# Placa_Final_Embebidos_MCU.net
KiCad netlist of a schematic drawn in Altium Designer
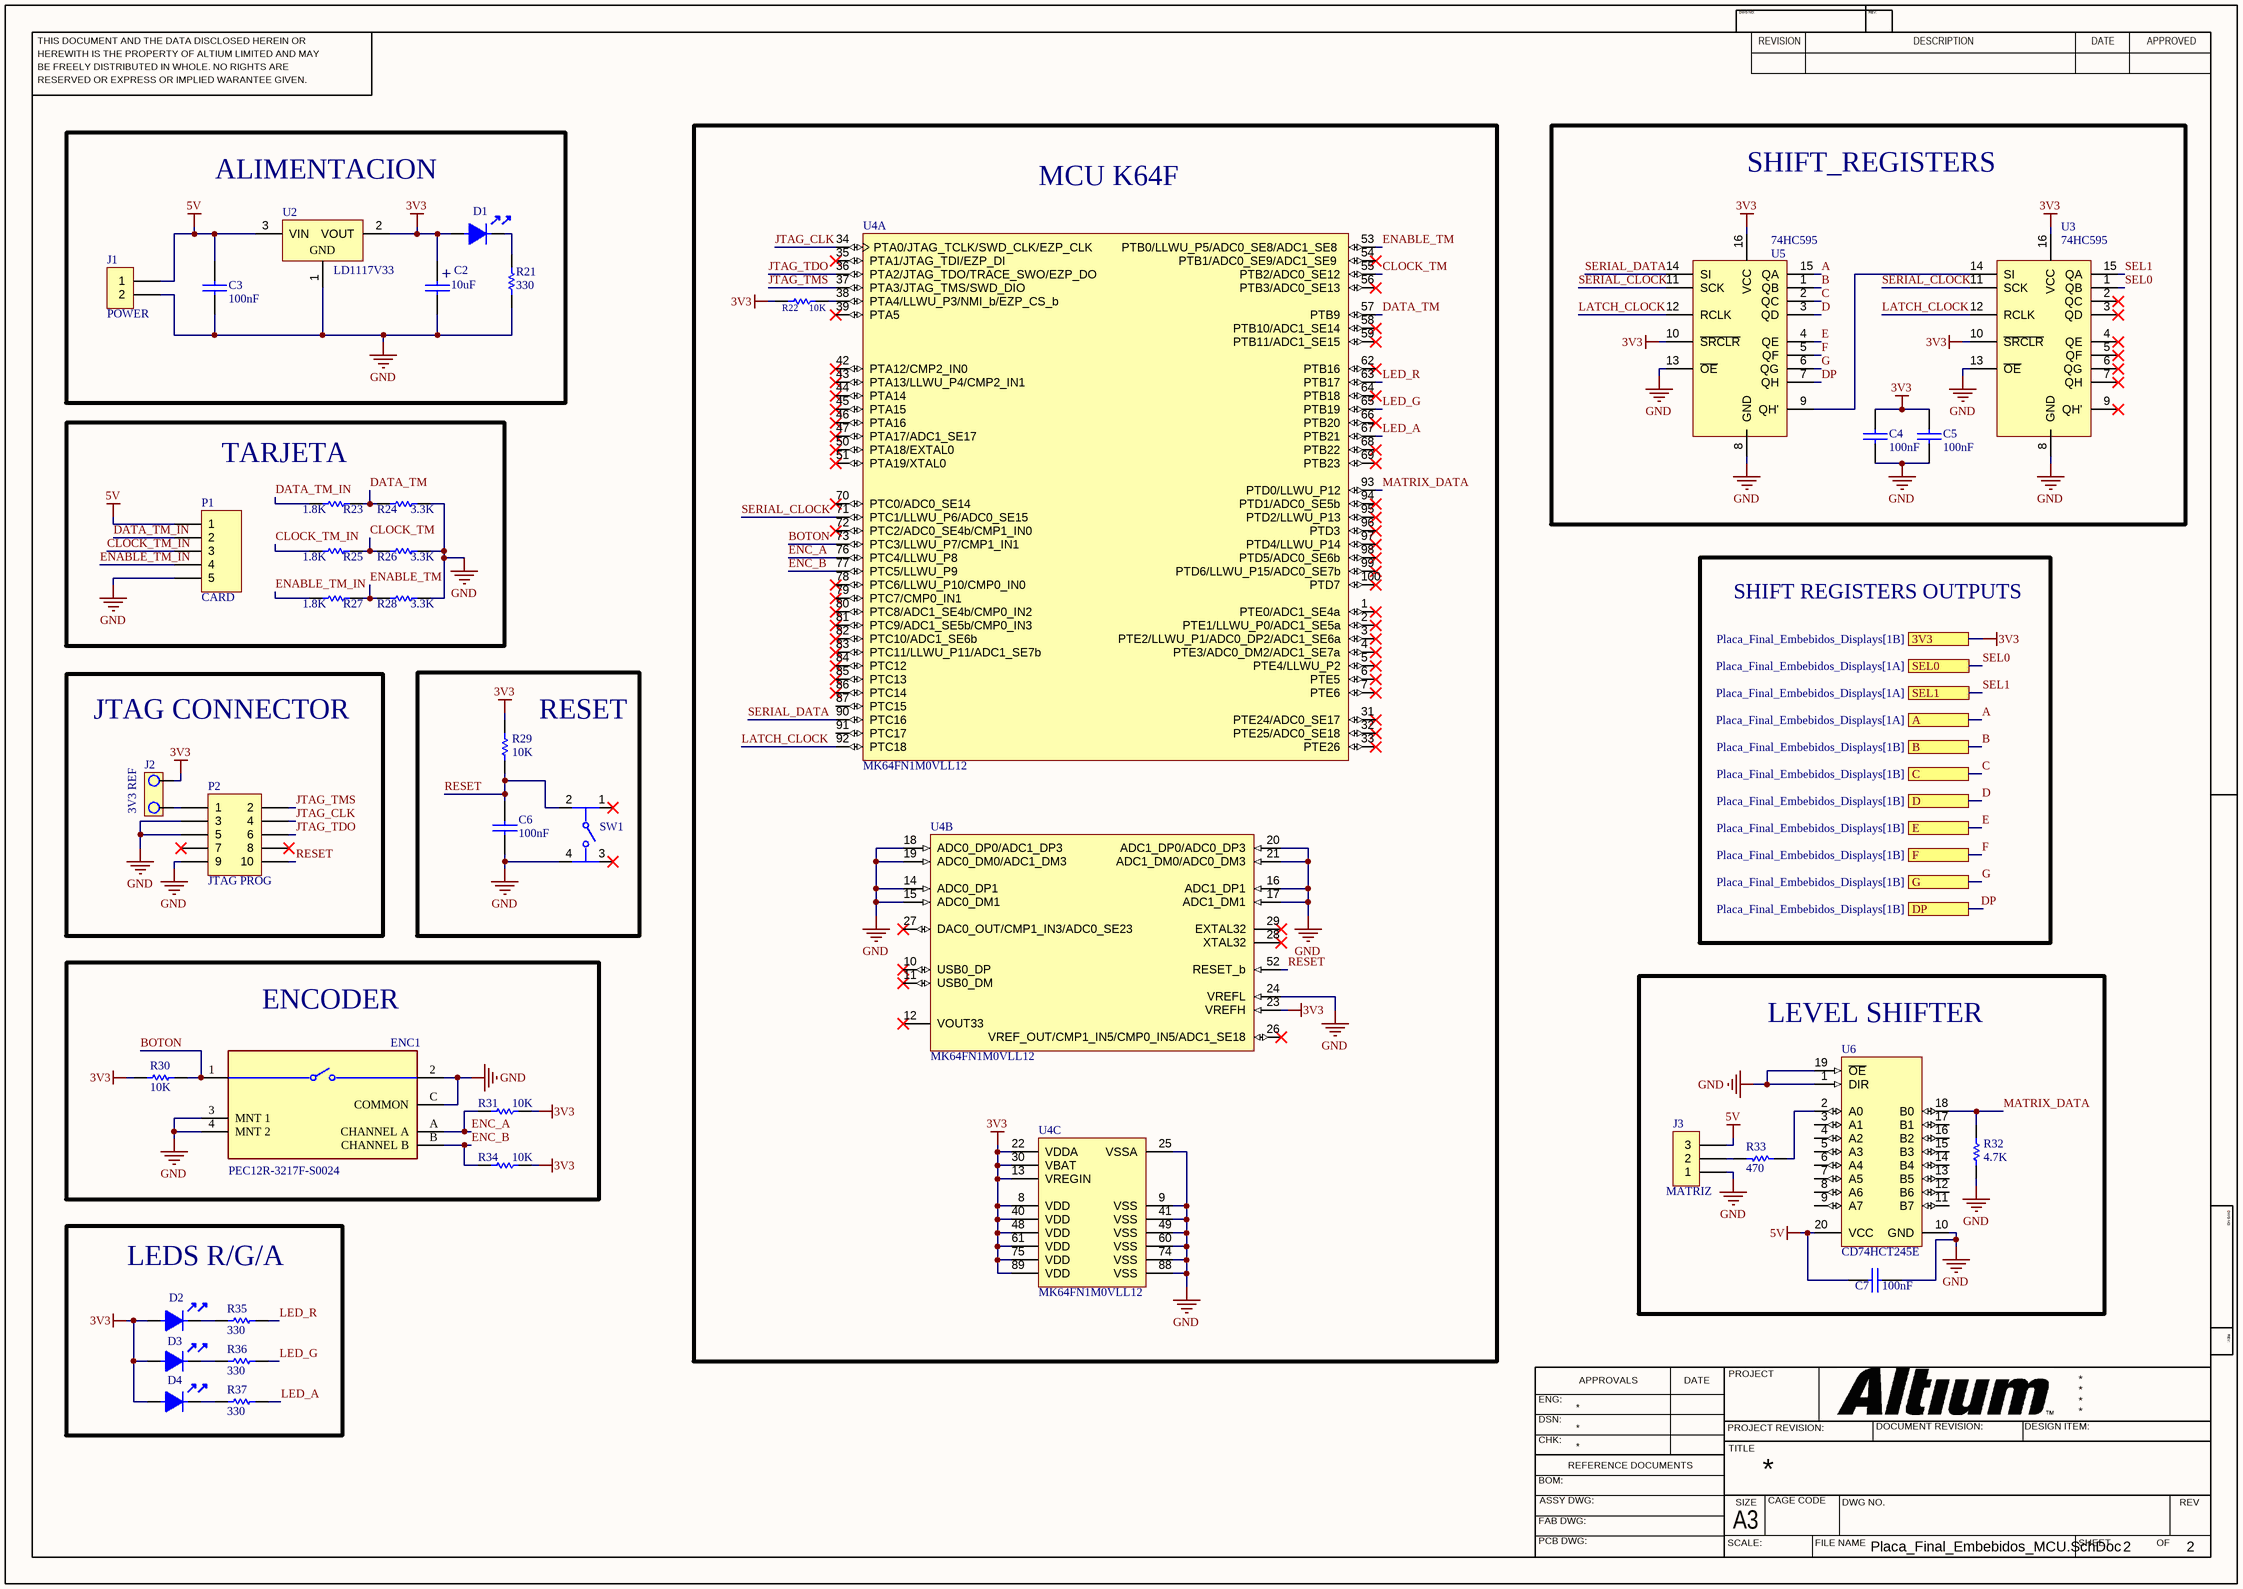
[diagram p0: Placa_Final_Embebidos_MCU.SchDoc]

(export (version "E")
  (design (tool "Eeschema 10.0.6"))
  (components
    (comp (ref "C2") (value "10uF") (footprint "CAP100RP") (libsource (lib "LIB PIO IX") (part "CAPPOL")))
    (comp (ref "C3") (value "100nF") (footprint "CAP200") (libsource (lib "LIB PIO IX") (part "CAP")))
    (comp (ref "C4") (value "100nF") (footprint "CAP200") (libsource (lib "LIB PIO IX") (part "CAP")))
    (comp (ref "C5") (value "100nF") (footprint "CAP200") (libsource (lib "LIB PIO IX") (part "CAP")))
    (comp (ref "C6") (value "100nF") (footprint "CAP200") (libsource (lib "LIB PIO IX") (part "CAP")))
    (comp (ref "C7") (value "100nF") (footprint "CAP200") (libsource (lib "LIB PIO IX") (part "CAP")))
    (comp (ref "D1") (value "~") (footprint "LED3") (libsource (lib "LIB PIO IX") (part "LED")))
    (comp (ref "D2") (value "~") (footprint "LED3") (libsource (lib "LIB PIO IX") (part "LED")))
    (comp (ref "D3") (value "~") (footprint "LED3") (libsource (lib "LIB PIO IX") (part "LED")))
    (comp (ref "D4") (value "~") (footprint "LED3") (libsource (lib "LIB PIO IX") (part "LED")))
    (comp (ref "ENC1")
      (value "PEC12R-3217F-S0024")
      (footprint "FP-PEC12R-3217F-S0024-MFG")
      (description "ROTARY ENCODER")
      (libsource (lib "Altium Content Vault") (part "795c46dd6d7d77f565e7c060d07d204"))
    )
    (comp (ref "J1") (value "POWER") (footprint "BORNERA2") (libsource (lib "LIBEBAL") (part "BORNERA 2")))
    (comp (ref "J2") (value "3V3 REF") (footprint "JUMPER2") (libsource (lib "LIBEBAL") (part "JUMPER")))
    (comp (ref "J3") (value "MATRIZ") (footprint "SIP3") (libsource (lib "LIBEBAL") (part "CON3")))
    (comp (ref "P1")
      (value "CARD")
      (footprint "HDR1X5")
      (description "Header, 5-Pin")
      (fields (field (name "PUBLISHER") "Altium Limited"))
      (libsource (lib "Miscellaneous Connectors") (part "Header 5"))
    )
    (comp (ref "P2")
      (value "JTAG PROG")
      (footprint "HDR2X5")
      (description "Header, 5-Pin, Dual row")
      (fields (field (name "PUBLISHER") "Altium Limited"))
      (libsource (lib "Miscellaneous Connectors") (part "Header 5X2"))
    )
    (comp (ref "R21") (value "330") (footprint "RES400") (libsource (lib "LIB PIO IX") (part "RES")))
    (comp (ref "R22") (value "10K") (footprint "RES400") (libsource (lib "LIB PIO IX") (part "RES")))
    (comp (ref "R23") (value "1.8K") (footprint "RES400") (libsource (lib "LIB PIO IX") (part "RES")))
    (comp (ref "R24") (value "3.3K") (footprint "RES400") (libsource (lib "LIB PIO IX") (part "RES")))
    (comp (ref "R25") (value "1.8K") (footprint "RES400") (libsource (lib "LIB PIO IX") (part "RES")))
    (comp (ref "R26") (value "3.3K") (footprint "RES400") (libsource (lib "LIB PIO IX") (part "RES")))
    (comp (ref "R27") (value "1.8K") (footprint "RES400") (libsource (lib "LIB PIO IX") (part "RES")))
    (comp (ref "R28") (value "3.3K") (footprint "RES400") (libsource (lib "LIB PIO IX") (part "RES")))
    (comp (ref "R29") (value "10K") (footprint "RES400") (libsource (lib "LIB PIO IX") (part "RES")))
    (comp (ref "R30") (value "10K") (footprint "RES400") (libsource (lib "LIB PIO IX") (part "RES")))
    (comp (ref "R31") (value "10K") (footprint "RES400") (libsource (lib "LIB PIO IX") (part "RES")))
    (comp (ref "R32") (value "4.7K") (footprint "RES400") (libsource (lib "LIB PIO IX") (part "RES")))
    (comp (ref "R33") (value "470") (footprint "RES400") (libsource (lib "LIB PIO IX") (part "RES")))
    (comp (ref "R34") (value "10K") (footprint "RES400") (libsource (lib "LIB PIO IX") (part "RES")))
    (comp (ref "R35") (value "330") (footprint "RES400") (libsource (lib "LIB PIO IX") (part "RES")))
    (comp (ref "R36") (value "330") (footprint "RES400") (libsource (lib "LIB PIO IX") (part "RES")))
    (comp (ref "R37") (value "330") (footprint "RES400") (libsource (lib "LIB PIO IX") (part "RES")))
    (comp (ref "SW1")
      (value "~")
      (footprint "FP-B3F-1055-MFG")
      (description "SWITCH TACTILE SPST-NO 0.05A 24V")
      (libsource (lib "Altium Content Vault") (part "b8895f3f4cefb76e1819d2863dba89b"))
    )
    (comp (ref "U2")
      (value "LD1117V33")
      (footprint "TO220")
      (description "Fixed Low Drop Positive Voltage Regulator, 3.3V, 3-Pin TO-220")
      (libsource (lib "Altium Content Vault") (part "PM-REG-LD1117V-SIL3"))
    )
    (comp (ref "U3") (value "74HC595") (footprint "DIP16") (libsource (lib "LIBEBAL") (part "74HC595")))
    (comp (ref "U4")
      (value "MK64FN1M0VLL12")
      (footprint "PCB_BOARD_K64F_MIRROR:K64F_DevBoard_Headers_MIRROR")
      (fields (field (name "MANUFACTURER") "Freescale Semiconductor"))
      (libsource (lib "K64F_Board_MIRROR") (part "CMP-0182-00049-1"))
    )
    (comp (ref "U5") (value "74HC595") (footprint "DIP16") (libsource (lib "LIBEBAL") (part "74HC595")))
    (comp (ref "U6")
      (value "CD74HCT245E")
      (footprint "N0020A")
      (description "High Speed CMOS Logic Non-Inverting Octal-Bus Transceiver with 3-State Outpus, N0020A, TUBE")
      (fields
        (field (name "GENERIC PART NUMBER") "CD74HCT245")
        (field (name "MANUFACTURER") "Texas Instruments")
      )
      (libsource (lib "Altium Content Vault") (part "TI-CD54_74XXX245_640-20"))
    )
  )
  (nets
    (net (code "1") (name "/A") (class "Default")
      (node (ref "U5") (pin "15") (pinfunction "QA_15") (pintype "passive"))
    )
    (net (code "2") (name "/B") (class "Default")
      (node (ref "U5") (pin "1") (pinfunction "QB_1") (pintype "passive"))
    )
    (net (code "3") (name "/BOTON") (class "Default")
      (node (ref "ENC1") (pin "1") (pinfunction "1_1") (pintype "passive"))
      (node (ref "R30") (pin "2") (pinfunction "2_2") (pintype "passive"))
      (node (ref "U4") (pin "73") (pinfunction "PTC3/LLWU_P7/CMP1_IN1_73") (pintype "bidirectional"))
    )
    (net (code "4") (name "/C") (class "Default")
      (node (ref "U5") (pin "2") (pinfunction "QC_2") (pintype "passive"))
    )
    (net (code "5") (name "/CLOCK_TM") (class "Default")
      (node (ref "R25") (pin "2") (pinfunction "2_2") (pintype "passive"))
      (node (ref "R26") (pin "1") (pinfunction "1_1") (pintype "passive"))
      (node (ref "U4") (pin "55") (pinfunction "PTB2/ADC0_SE12_55") (pintype "bidirectional"))
    )
    (net (code "6") (name "/CLOCK_TM_IN") (class "Default")
      (node (ref "P1") (pin "3") (pinfunction "3_3") (pintype "passive"))
      (node (ref "R25") (pin "1") (pinfunction "1_1") (pintype "passive"))
    )
    (net (code "7") (name "/D") (class "Default")
      (node (ref "U5") (pin "3") (pinfunction "QD_3") (pintype "passive"))
    )
    (net (code "8") (name "/DATA_TM") (class "Default")
      (node (ref "R23") (pin "2") (pinfunction "2_2") (pintype "passive"))
      (node (ref "R24") (pin "1") (pinfunction "1_1") (pintype "passive"))
      (node (ref "U4") (pin "57") (pinfunction "PTB9_57") (pintype "bidirectional"))
    )
    (net (code "9") (name "/DATA_TM_IN") (class "Default")
      (node (ref "P1") (pin "2") (pinfunction "2_2") (pintype "passive"))
      (node (ref "R23") (pin "1") (pinfunction "1_1") (pintype "passive"))
    )
    (net (code "10") (name "/DP") (class "Default")
      (node (ref "U5") (pin "7") (pinfunction "QH_7") (pintype "passive"))
    )
    (net (code "11") (name "/E") (class "Default")
      (node (ref "U5") (pin "4") (pinfunction "QE_4") (pintype "passive"))
    )
    (net (code "12") (name "/ENABLE_TM") (class "Default")
      (node (ref "R27") (pin "2") (pinfunction "2_2") (pintype "passive"))
      (node (ref "R28") (pin "1") (pinfunction "1_1") (pintype "passive"))
      (node (ref "U4") (pin "53") (pinfunction "PTB0/LLWU_P5/ADC0_SE8/ADC1_SE8_53") (pintype "bidirectional"))
    )
    (net (code "13") (name "/ENABLE_TM_IN") (class "Default")
      (node (ref "P1") (pin "4") (pinfunction "4_4") (pintype "passive"))
      (node (ref "R27") (pin "1") (pinfunction "1_1") (pintype "passive"))
    )
    (net (code "14") (name "/ENC_A") (class "Default")
      (node (ref "ENC1") (pin "A") (pinfunction "CHANNEL_A_A") (pintype "passive"))
      (node (ref "R31") (pin "1") (pinfunction "1_1") (pintype "passive"))
      (node (ref "U4") (pin "76") (pinfunction "PTC4/LLWU_P8_76") (pintype "bidirectional"))
    )
    (net (code "15") (name "/ENC_B") (class "Default")
      (node (ref "ENC1") (pin "B") (pinfunction "CHANNEL_B_B") (pintype "passive"))
      (node (ref "R34") (pin "2") (pinfunction "2_2") (pintype "passive"))
      (node (ref "U4") (pin "77") (pinfunction "PTC5/LLWU_P9_77") (pintype "bidirectional"))
    )
    (net (code "16") (name "/F") (class "Default")
      (node (ref "U5") (pin "5") (pinfunction "QF_5") (pintype "passive"))
    )
    (net (code "17") (name "/G") (class "Default")
      (node (ref "U5") (pin "6") (pinfunction "QG_6") (pintype "passive"))
    )
    (net (code "18") (name "/JTAG_CLK") (class "Default")
      (node (ref "P2") (pin "4") (pinfunction "4_4") (pintype "passive"))
      (node (ref "U4") (pin "34") (pinfunction "PTA0/JTAG_TCLK/SWD_CLK/EZP_CLK_34") (pintype "bidirectional"))
    )
    (net (code "19") (name "/JTAG_TDO") (class "Default")
      (node (ref "P2") (pin "6") (pinfunction "6_6") (pintype "passive"))
      (node (ref "U4") (pin "36") (pinfunction "PTA2/JTAG_TDO/TRACE_SWO/EZP_DO_36") (pintype "bidirectional"))
    )
    (net (code "20") (name "/JTAG_TMS") (class "Default")
      (node (ref "P2") (pin "2") (pinfunction "2_2") (pintype "passive"))
      (node (ref "U4") (pin "37") (pinfunction "PTA3/JTAG_TMS/SWD_DIO_37") (pintype "bidirectional"))
    )
    (net (code "21") (name "/LATCH_CLOCK") (class "Default")
      (node (ref "U3") (pin "12") (pinfunction "RCLK_12") (pintype "passive"))
      (node (ref "U4") (pin "92") (pinfunction "PTC18_92") (pintype "bidirectional"))
      (node (ref "U5") (pin "12") (pinfunction "RCLK_12") (pintype "passive"))
    )
    (net (code "22") (name "/LED_A") (class "Default")
      (node (ref "R37") (pin "2") (pinfunction "2_2") (pintype "passive"))
      (node (ref "U4") (pin "67") (pinfunction "PTB21_67") (pintype "bidirectional"))
    )
    (net (code "23") (name "/LED_G") (class "Default")
      (node (ref "R36") (pin "2") (pinfunction "2_2") (pintype "passive"))
      (node (ref "U4") (pin "65") (pinfunction "PTB19_65") (pintype "bidirectional"))
    )
    (net (code "24") (name "/LED_R") (class "Default")
      (node (ref "R35") (pin "2") (pinfunction "2_2") (pintype "passive"))
      (node (ref "U4") (pin "63") (pinfunction "PTB17_63") (pintype "bidirectional"))
    )
    (net (code "25") (name "/MATRIX_DATA") (class "Default")
      (node (ref "R32") (pin "2") (pinfunction "2_2") (pintype "passive"))
      (node (ref "U4") (pin "93") (pinfunction "PTD0/LLWU_P12_93") (pintype "bidirectional"))
      (node (ref "U6") (pin "18") (pinfunction "B0_18") (pintype "bidirectional"))
    )
    (net (code "26") (name "/RESET") (class "Default")
      (node (ref "C6") (pin "1") (pinfunction "1_1") (pintype "passive"))
      (node (ref "P2") (pin "10") (pinfunction "10_10") (pintype "passive"))
      (node (ref "R29") (pin "1") (pinfunction "1_1") (pintype "passive"))
      (node (ref "SW1") (pin "2") (pinfunction "2_2") (pintype "passive"))
      (node (ref "U4") (pin "52") (pinfunction "RESET_b_52") (pintype "input"))
    )
    (net (code "27") (name "/SEL0") (class "Default")
      (node (ref "U3") (pin "1") (pinfunction "QB_1") (pintype "passive"))
    )
    (net (code "28") (name "/SEL1") (class "Default")
      (node (ref "U3") (pin "15") (pinfunction "QA_15") (pintype "passive"))
    )
    (net (code "29") (name "/SERIAL_CLOCK") (class "Default")
      (node (ref "U3") (pin "11") (pinfunction "SCK_11") (pintype "passive"))
      (node (ref "U4") (pin "71") (pinfunction "PTC1/LLWU_P6/ADC0_SE15_71") (pintype "bidirectional"))
      (node (ref "U5") (pin "11") (pinfunction "SCK_11") (pintype "passive"))
    )
    (net (code "30") (name "/SERIAL_DATA") (class "Default")
      (node (ref "U4") (pin "90") (pinfunction "PTC16_90") (pintype "bidirectional"))
      (node (ref "U5") (pin "14") (pinfunction "SI_14") (pintype "passive"))
    )
    (net (code "31") (name "3V3") (class "Default")
      (node (ref "C2") (pin "1") (pinfunction "1_1") (pintype "passive"))
      (node (ref "C4") (pin "2") (pinfunction "2_2") (pintype "passive"))
      (node (ref "C5") (pin "2") (pinfunction "2_2") (pintype "passive"))
      (node (ref "D1") (pin "1") (pinfunction "1_1") (pintype "passive"))
      (node (ref "D2") (pin "1") (pinfunction "1_1") (pintype "passive"))
      (node (ref "D3") (pin "1") (pinfunction "1_1") (pintype "passive"))
      (node (ref "D4") (pin "1") (pinfunction "1_1") (pintype "passive"))
      (node (ref "J2") (pin "1") (pinfunction "1_1") (pintype "passive"))
      (node (ref "R22") (pin "2") (pinfunction "2_2") (pintype "passive"))
      (node (ref "R29") (pin "2") (pinfunction "2_2") (pintype "passive"))
      (node (ref "R30") (pin "1") (pinfunction "1_1") (pintype "passive"))
      (node (ref "R31") (pin "2") (pinfunction "2_2") (pintype "passive"))
      (node (ref "R34") (pin "1") (pinfunction "1_1") (pintype "passive"))
      (node (ref "U2") (pin "2") (pinfunction "VOUT_2") (pintype "power_in"))
      (node (ref "U3") (pin "10") (pinfunction "~{SRCLR}_10") (pintype "passive"))
      (node (ref "U3") (pin "16") (pinfunction "VCC_16") (pintype "passive"))
      (node (ref "U4") (pin "13") (pinfunction "VREGIN_13") (pintype "power_in"))
      (node (ref "U4") (pin "22") (pinfunction "VDDA_22") (pintype "power_in"))
      (node (ref "U4") (pin "23") (pinfunction "VREFH_23") (pintype "input"))
      (node (ref "U4") (pin "30") (pinfunction "VBAT_30") (pintype "power_in"))
      (node (ref "U4") (pin "40") (pinfunction "VDD_40") (pintype "power_in"))
      (node (ref "U4") (pin "48") (pinfunction "VDD_48") (pintype "power_in"))
      (node (ref "U4") (pin "61") (pinfunction "VDD_61") (pintype "power_in"))
      (node (ref "U4") (pin "75") (pinfunction "VDD_75") (pintype "power_in"))
      (node (ref "U4") (pin "8") (pinfunction "VDD_8") (pintype "power_in"))
      (node (ref "U4") (pin "89") (pinfunction "VDD_89") (pintype "power_in"))
      (node (ref "U5") (pin "10") (pinfunction "~{SRCLR}_10") (pintype "passive"))
      (node (ref "U5") (pin "16") (pinfunction "VCC_16") (pintype "passive"))
    )
    (net (code "32") (name "5V") (class "Default")
      (node (ref "C3") (pin "1") (pinfunction "1_1") (pintype "passive"))
      (node (ref "C7") (pin "1") (pinfunction "1_1") (pintype "passive"))
      (node (ref "J1") (pin "1") (pinfunction "1_1") (pintype "passive"))
      (node (ref "J3") (pin "3") (pinfunction "3_3") (pintype "passive"))
      (node (ref "P1") (pin "1") (pinfunction "1_1") (pintype "passive"))
      (node (ref "U2") (pin "3") (pinfunction "VIN_3") (pintype "power_in"))
      (node (ref "U6") (pin "20") (pinfunction "VCC_20") (pintype "power_in"))
    )
    (net (code "33") (name "GND") (class "Default")
      (node (ref "C2") (pin "2") (pinfunction "2_2") (pintype "passive"))
      (node (ref "C3") (pin "2") (pinfunction "2_2") (pintype "passive"))
      (node (ref "C4") (pin "1") (pinfunction "1_1") (pintype "passive"))
      (node (ref "C5") (pin "1") (pinfunction "1_1") (pintype "passive"))
      (node (ref "C6") (pin "2") (pinfunction "2_2") (pintype "passive"))
      (node (ref "C7") (pin "2") (pinfunction "2_2") (pintype "passive"))
      (node (ref "ENC1") (pin "2") (pinfunction "2_2") (pintype "passive"))
      (node (ref "ENC1") (pin "3") (pinfunction "MNT_1_3") (pintype "passive"))
      (node (ref "ENC1") (pin "4") (pinfunction "MNT_2_4") (pintype "passive"))
      (node (ref "ENC1") (pin "C") (pinfunction "COMMON_C") (pintype "passive"))
      (node (ref "J1") (pin "2") (pinfunction "2_2") (pintype "passive"))
      (node (ref "J3") (pin "1") (pinfunction "1_1") (pintype "passive"))
      (node (ref "P1") (pin "5") (pinfunction "5_5") (pintype "passive"))
      (node (ref "P2") (pin "3") (pinfunction "3_3") (pintype "passive"))
      (node (ref "P2") (pin "5") (pinfunction "5_5") (pintype "passive"))
      (node (ref "P2") (pin "9") (pinfunction "9_9") (pintype "passive"))
      (node (ref "R21") (pin "2") (pinfunction "2_2") (pintype "passive"))
      (node (ref "R24") (pin "2") (pinfunction "2_2") (pintype "passive"))
      (node (ref "R26") (pin "2") (pinfunction "2_2") (pintype "passive"))
      (node (ref "R28") (pin "2") (pinfunction "2_2") (pintype "passive"))
      (node (ref "R32") (pin "1") (pinfunction "1_1") (pintype "passive"))
      (node (ref "SW1") (pin "4") (pinfunction "4_4") (pintype "passive"))
      (node (ref "U2") (pin "1") (pinfunction "GND_1") (pintype "power_in"))
      (node (ref "U3") (pin "13") (pinfunction "~{OE}_13") (pintype "passive"))
      (node (ref "U3") (pin "8") (pinfunction "GND_8") (pintype "passive"))
      (node (ref "U4") (pin "14") (pinfunction "ADC0_DP1_14") (pintype "input"))
      (node (ref "U4") (pin "15") (pinfunction "ADC0_DM1_15") (pintype "input"))
      (node (ref "U4") (pin "16") (pinfunction "ADC1_DP1_16") (pintype "input"))
      (node (ref "U4") (pin "17") (pinfunction "ADC1_DM1_17") (pintype "input"))
      (node (ref "U4") (pin "18") (pinfunction "ADC0_DP0/ADC1_DP3_18") (pintype "input"))
      (node (ref "U4") (pin "19") (pinfunction "ADC0_DM0/ADC1_DM3_19") (pintype "input"))
      (node (ref "U4") (pin "20") (pinfunction "ADC1_DP0/ADC0_DP3_20") (pintype "input"))
      (node (ref "U4") (pin "21") (pinfunction "ADC1_DM0/ADC0_DM3_21") (pintype "input"))
      (node (ref "U4") (pin "24") (pinfunction "VREFL_24") (pintype "input"))
      (node (ref "U4") (pin "25") (pinfunction "VSSA_25") (pintype "power_in"))
      (node (ref "U4") (pin "41") (pinfunction "VSS_41") (pintype "power_in"))
      (node (ref "U4") (pin "49") (pinfunction "VSS_49") (pintype "power_in"))
      (node (ref "U4") (pin "60") (pinfunction "VSS_60") (pintype "power_in"))
      (node (ref "U4") (pin "74") (pinfunction "VSS_74") (pintype "power_in"))
      (node (ref "U4") (pin "88") (pinfunction "VSS_88") (pintype "power_in"))
      (node (ref "U4") (pin "9") (pinfunction "VSS_9") (pintype "power_in"))
      (node (ref "U5") (pin "13") (pinfunction "~{OE}_13") (pintype "passive"))
      (node (ref "U5") (pin "8") (pinfunction "GND_8") (pintype "passive"))
      (node (ref "U6") (pin "1") (pinfunction "DIR_1") (pintype "input"))
      (node (ref "U6") (pin "10") (pinfunction "GND_10") (pintype "power_in"))
      (node (ref "U6") (pin "19") (pinfunction "~{OE}_19") (pintype "input"))
    )
    (net (code "34") (name "Net-(D1-Pad2)") (class "Default")
      (node (ref "D1") (pin "2") (pinfunction "2_2") (pintype "passive"))
      (node (ref "R21") (pin "1") (pinfunction "1_1") (pintype "passive"))
    )
    (net (code "35") (name "Net-(D2-Pad2)") (class "Default")
      (node (ref "D2") (pin "2") (pinfunction "2_2") (pintype "passive"))
      (node (ref "R35") (pin "1") (pinfunction "1_1") (pintype "passive"))
    )
    (net (code "36") (name "Net-(D3-Pad2)") (class "Default")
      (node (ref "D3") (pin "2") (pinfunction "2_2") (pintype "passive"))
      (node (ref "R36") (pin "1") (pinfunction "1_1") (pintype "passive"))
    )
    (net (code "37") (name "Net-(D4-Pad2)") (class "Default")
      (node (ref "D4") (pin "2") (pinfunction "2_2") (pintype "passive"))
      (node (ref "R37") (pin "1") (pinfunction "1_1") (pintype "passive"))
    )
    (net (code "38") (name "Net-(J2-Pad2)") (class "Default")
      (node (ref "J2") (pin "2") (pinfunction "2_2") (pintype "passive"))
      (node (ref "P2") (pin "1") (pinfunction "1_1") (pintype "passive"))
    )
    (net (code "39") (name "Net-(J3-Pad2)") (class "Default")
      (node (ref "J3") (pin "2") (pinfunction "2_2") (pintype "passive"))
      (node (ref "R33") (pin "1") (pinfunction "1_1") (pintype "passive"))
    )
    (net (code "40") (name "Net-(U3-SI)") (class "Default")
      (node (ref "U3") (pin "14") (pinfunction "SI_14") (pintype "passive"))
      (node (ref "U5") (pin "9") (pinfunction "QH'_9") (pintype "passive"))
    )
    (net (code "41") (name "Net-(U4A-PTA4{slash}LLWU_P3{slash}NMI_b{slash}EZP_CS_b)") (class "Default")
      (node (ref "R22") (pin "1") (pinfunction "1_1") (pintype "passive"))
      (node (ref "U4") (pin "38") (pinfunction "PTA4/LLWU_P3/NMI_b/EZP_CS_b_38") (pintype "bidirectional"))
    )
    (net (code "42") (name "Net-(U6-A0)") (class "Default")
      (node (ref "R33") (pin "2") (pinfunction "2_2") (pintype "passive"))
      (node (ref "U6") (pin "2") (pinfunction "A0_2") (pintype "bidirectional"))
    )
    (net (code "43") (name "unconnected-(P2-Pad7)") (class "Default")
      (node (ref "P2") (pin "7") (pinfunction "7_7") (pintype "passive+no_connect"))
    )
    (net (code "44") (name "unconnected-(P2-Pad8)") (class "Default")
      (node (ref "P2") (pin "8") (pinfunction "8_8") (pintype "passive+no_connect"))
    )
    (net (code "45") (name "unconnected-(SW1-Pad1)") (class "Default")
      (node (ref "SW1") (pin "1") (pinfunction "1_1") (pintype "passive+no_connect"))
    )
    (net (code "46") (name "unconnected-(SW1-Pad3)") (class "Default")
      (node (ref "SW1") (pin "3") (pinfunction "3_3") (pintype "passive+no_connect"))
    )
    (net (code "47") (name "unconnected-(U3-QC-Pad2)") (class "Default")
      (node (ref "U3") (pin "2") (pinfunction "QC_2") (pintype "passive+no_connect"))
    )
    (net (code "48") (name "unconnected-(U3-QD-Pad3)") (class "Default")
      (node (ref "U3") (pin "3") (pinfunction "QD_3") (pintype "passive+no_connect"))
    )
    (net (code "49") (name "unconnected-(U3-QE-Pad4)") (class "Default")
      (node (ref "U3") (pin "4") (pinfunction "QE_4") (pintype "passive+no_connect"))
    )
    (net (code "50") (name "unconnected-(U3-QF-Pad5)") (class "Default")
      (node (ref "U3") (pin "5") (pinfunction "QF_5") (pintype "passive+no_connect"))
    )
    (net (code "51") (name "unconnected-(U3-QG-Pad6)") (class "Default")
      (node (ref "U3") (pin "6") (pinfunction "QG_6") (pintype "passive+no_connect"))
    )
    (net (code "52") (name "unconnected-(U3-QH'-Pad9)") (class "Default")
      (node (ref "U3") (pin "9") (pinfunction "QH'_9") (pintype "passive+no_connect"))
    )
    (net (code "53") (name "unconnected-(U3-QH-Pad7)") (class "Default")
      (node (ref "U3") (pin "7") (pinfunction "QH_7") (pintype "passive+no_connect"))
    )
    (net (code "54") (name "unconnected-(U4A-PTA1{slash}JTAG_TDI{slash}EZP_DI-Pad35)") (class "Default")
      (node (ref "U4") (pin "35") (pinfunction "PTA1/JTAG_TDI/EZP_DI_35") (pintype "bidirectional+no_connect"))
    )
    (net (code "55") (name "unconnected-(U4A-PTA5-Pad39)") (class "Default")
      (node (ref "U4") (pin "39") (pinfunction "PTA5_39") (pintype "bidirectional+no_connect"))
    )
    (net (code "56") (name "unconnected-(U4A-PTA12{slash}CMP2_IN0-Pad42)") (class "Default")
      (node (ref "U4") (pin "42") (pinfunction "PTA12/CMP2_IN0_42") (pintype "bidirectional+no_connect"))
    )
    (net (code "57") (name "unconnected-(U4A-PTA13{slash}LLWU_P4{slash}CMP2_IN1-Pad43)") (class "Default")
      (node (ref "U4") (pin "43") (pinfunction "PTA13/LLWU_P4/CMP2_IN1_43") (pintype "bidirectional+no_connect"))
    )
    (net (code "58") (name "unconnected-(U4A-PTA14-Pad44)") (class "Default")
      (node (ref "U4") (pin "44") (pinfunction "PTA14_44") (pintype "bidirectional+no_connect"))
    )
    (net (code "59") (name "unconnected-(U4A-PTA15-Pad45)") (class "Default")
      (node (ref "U4") (pin "45") (pinfunction "PTA15_45") (pintype "bidirectional+no_connect"))
    )
    (net (code "60") (name "unconnected-(U4A-PTA16-Pad46)") (class "Default")
      (node (ref "U4") (pin "46") (pinfunction "PTA16_46") (pintype "bidirectional+no_connect"))
    )
    (net (code "61") (name "unconnected-(U4A-PTA17{slash}ADC1_SE17-Pad47)") (class "Default")
      (node (ref "U4") (pin "47") (pinfunction "PTA17/ADC1_SE17_47") (pintype "bidirectional+no_connect"))
    )
    (net (code "62") (name "unconnected-(U4A-PTA18{slash}EXTAL0-Pad50)") (class "Default")
      (node (ref "U4") (pin "50") (pinfunction "PTA18/EXTAL0_50") (pintype "bidirectional+no_connect"))
    )
    (net (code "63") (name "unconnected-(U4A-PTA19{slash}XTAL0-Pad51)") (class "Default")
      (node (ref "U4") (pin "51") (pinfunction "PTA19/XTAL0_51") (pintype "bidirectional+no_connect"))
    )
    (net (code "64") (name "unconnected-(U4A-PTB1{slash}ADC0_SE9{slash}ADC1_SE9-Pad54)") (class "Default")
      (node (ref "U4") (pin "54") (pinfunction "PTB1/ADC0_SE9/ADC1_SE9_54") (pintype "bidirectional+no_connect"))
    )
    (net (code "65") (name "unconnected-(U4A-PTB3{slash}ADC0_SE13-Pad56)") (class "Default")
      (node (ref "U4") (pin "56") (pinfunction "PTB3/ADC0_SE13_56") (pintype "bidirectional+no_connect"))
    )
    (net (code "66") (name "unconnected-(U4A-PTB10{slash}ADC1_SE14-Pad58)") (class "Default")
      (node (ref "U4") (pin "58") (pinfunction "PTB10/ADC1_SE14_58") (pintype "bidirectional+no_connect"))
    )
    (net (code "67") (name "unconnected-(U4A-PTB11{slash}ADC1_SE15-Pad59)") (class "Default")
      (node (ref "U4") (pin "59") (pinfunction "PTB11/ADC1_SE15_59") (pintype "bidirectional+no_connect"))
    )
    (net (code "68") (name "unconnected-(U4A-PTB16-Pad62)") (class "Default")
      (node (ref "U4") (pin "62") (pinfunction "PTB16_62") (pintype "bidirectional+no_connect"))
    )
    (net (code "69") (name "unconnected-(U4A-PTB18-Pad64)") (class "Default")
      (node (ref "U4") (pin "64") (pinfunction "PTB18_64") (pintype "bidirectional+no_connect"))
    )
    (net (code "70") (name "unconnected-(U4A-PTB20-Pad66)") (class "Default")
      (node (ref "U4") (pin "66") (pinfunction "PTB20_66") (pintype "bidirectional+no_connect"))
    )
    (net (code "71") (name "unconnected-(U4A-PTB22-Pad68)") (class "Default")
      (node (ref "U4") (pin "68") (pinfunction "PTB22_68") (pintype "bidirectional+no_connect"))
    )
    (net (code "72") (name "unconnected-(U4A-PTB23-Pad69)") (class "Default")
      (node (ref "U4") (pin "69") (pinfunction "PTB23_69") (pintype "bidirectional+no_connect"))
    )
    (net (code "73") (name "unconnected-(U4A-PTC0{slash}ADC0_SE14-Pad70)") (class "Default")
      (node (ref "U4") (pin "70") (pinfunction "PTC0/ADC0_SE14_70") (pintype "bidirectional+no_connect"))
    )
    (net (code "74") (name "unconnected-(U4A-PTC2{slash}ADC0_SE4b{slash}CMP1_IN0-Pad72)") (class "Default")
      (node (ref "U4") (pin "72") (pinfunction "PTC2/ADC0_SE4b/CMP1_IN0_72") (pintype "bidirectional+no_connect"))
    )
    (net (code "75") (name "unconnected-(U4A-PTC6{slash}LLWU_P10{slash}CMP0_IN0-Pad78)") (class "Default")
      (node (ref "U4") (pin "78") (pinfunction "PTC6/LLWU_P10/CMP0_IN0_78") (pintype "bidirectional+no_connect"))
    )
    (net (code "76") (name "unconnected-(U4A-PTC7{slash}CMP0_IN1-Pad79)") (class "Default")
      (node (ref "U4") (pin "79") (pinfunction "PTC7/CMP0_IN1_79") (pintype "bidirectional+no_connect"))
    )
    (net (code "77") (name "unconnected-(U4A-PTC8{slash}ADC1_SE4b{slash}CMP0_IN2-Pad80)") (class "Default")
      (node (ref "U4") (pin "80") (pinfunction "PTC8/ADC1_SE4b/CMP0_IN2_80") (pintype "bidirectional+no_connect"))
    )
    (net (code "78") (name "unconnected-(U4A-PTC9{slash}ADC1_SE5b{slash}CMP0_IN3-Pad81)") (class "Default")
      (node (ref "U4") (pin "81") (pinfunction "PTC9/ADC1_SE5b/CMP0_IN3_81") (pintype "bidirectional+no_connect"))
    )
    (net (code "79") (name "unconnected-(U4A-PTC10{slash}ADC1_SE6b-Pad82)") (class "Default")
      (node (ref "U4") (pin "82") (pinfunction "PTC10/ADC1_SE6b_82") (pintype "bidirectional+no_connect"))
    )
    (net (code "80") (name "unconnected-(U4A-PTC11{slash}LLWU_P11{slash}ADC1_SE7b-Pad83)") (class "Default")
      (node (ref "U4") (pin "83") (pinfunction "PTC11/LLWU_P11/ADC1_SE7b_83") (pintype "bidirectional+no_connect"))
    )
    (net (code "81") (name "unconnected-(U4A-PTC12-Pad84)") (class "Default")
      (node (ref "U4") (pin "84") (pinfunction "PTC12_84") (pintype "bidirectional+no_connect"))
    )
    (net (code "82") (name "unconnected-(U4A-PTC13-Pad85)") (class "Default")
      (node (ref "U4") (pin "85") (pinfunction "PTC13_85") (pintype "bidirectional+no_connect"))
    )
    (net (code "83") (name "unconnected-(U4A-PTC14-Pad86)") (class "Default")
      (node (ref "U4") (pin "86") (pinfunction "PTC14_86") (pintype "bidirectional+no_connect"))
    )
    (net (code "84") (name "unconnected-(U4A-PTC15-Pad87)") (class "Default")
      (node (ref "U4") (pin "87") (pinfunction "PTC15_87") (pintype "bidirectional"))
    )
    (net (code "85") (name "unconnected-(U4A-PTC17-Pad91)") (class "Default")
      (node (ref "U4") (pin "91") (pinfunction "PTC17_91") (pintype "bidirectional"))
    )
    (net (code "86") (name "unconnected-(U4A-PTD1{slash}ADC0_SE5b-Pad94)") (class "Default")
      (node (ref "U4") (pin "94") (pinfunction "PTD1/ADC0_SE5b_94") (pintype "bidirectional+no_connect"))
    )
    (net (code "87") (name "unconnected-(U4A-PTD2{slash}LLWU_P13-Pad95)") (class "Default")
      (node (ref "U4") (pin "95") (pinfunction "PTD2/LLWU_P13_95") (pintype "bidirectional+no_connect"))
    )
    (net (code "88") (name "unconnected-(U4A-PTD3-Pad96)") (class "Default")
      (node (ref "U4") (pin "96") (pinfunction "PTD3_96") (pintype "bidirectional+no_connect"))
    )
    (net (code "89") (name "unconnected-(U4A-PTD4{slash}LLWU_P14-Pad97)") (class "Default")
      (node (ref "U4") (pin "97") (pinfunction "PTD4/LLWU_P14_97") (pintype "bidirectional+no_connect"))
    )
    (net (code "90") (name "unconnected-(U4A-PTD5{slash}ADC0_SE6b-Pad98)") (class "Default")
      (node (ref "U4") (pin "98") (pinfunction "PTD5/ADC0_SE6b_98") (pintype "bidirectional+no_connect"))
    )
    (net (code "91") (name "unconnected-(U4A-PTD6{slash}LLWU_P15{slash}ADC0_SE7b-Pad99)") (class "Default")
      (node (ref "U4") (pin "99") (pinfunction "PTD6/LLWU_P15/ADC0_SE7b_99") (pintype "bidirectional+no_connect"))
    )
    (net (code "92") (name "unconnected-(U4A-PTD7-Pad100)") (class "Default")
      (node (ref "U4") (pin "100") (pinfunction "PTD7_100") (pintype "bidirectional+no_connect"))
    )
    (net (code "93") (name "unconnected-(U4A-PTE0{slash}ADC1_SE4a-Pad1)") (class "Default")
      (node (ref "U4") (pin "1") (pinfunction "PTE0/ADC1_SE4a_1") (pintype "bidirectional+no_connect"))
    )
    (net (code "94") (name "unconnected-(U4A-PTE1{slash}LLWU_P0{slash}ADC1_SE5a-Pad2)") (class "Default")
      (node (ref "U4") (pin "2") (pinfunction "PTE1/LLWU_P0/ADC1_SE5a_2") (pintype "bidirectional+no_connect"))
    )
    (net (code "95") (name "unconnected-(U4A-PTE2{slash}LLWU_P1{slash}ADC0_DP2{slash}ADC1_SE6a-Pad3)") (class "Default")
      (node (ref "U4") (pin "3") (pinfunction "PTE2/LLWU_P1/ADC0_DP2/ADC1_SE6a_3") (pintype "bidirectional+no_connect"))
    )
    (net (code "96") (name "unconnected-(U4A-PTE3{slash}ADC0_DM2{slash}ADC1_SE7a-Pad4)") (class "Default")
      (node (ref "U4") (pin "4") (pinfunction "PTE3/ADC0_DM2/ADC1_SE7a_4") (pintype "bidirectional+no_connect"))
    )
    (net (code "97") (name "unconnected-(U4A-PTE4{slash}LLWU_P2-Pad5)") (class "Default")
      (node (ref "U4") (pin "5") (pinfunction "PTE4/LLWU_P2_5") (pintype "bidirectional+no_connect"))
    )
    (net (code "98") (name "unconnected-(U4A-PTE5-Pad6)") (class "Default")
      (node (ref "U4") (pin "6") (pinfunction "PTE5_6") (pintype "bidirectional+no_connect"))
    )
    (net (code "99") (name "unconnected-(U4A-PTE6-Pad7)") (class "Default")
      (node (ref "U4") (pin "7") (pinfunction "PTE6_7") (pintype "bidirectional+no_connect"))
    )
    (net (code "100") (name "unconnected-(U4A-PTE24{slash}ADC0_SE17-Pad31)") (class "Default")
      (node (ref "U4") (pin "31") (pinfunction "PTE24/ADC0_SE17_31") (pintype "bidirectional+no_connect"))
    )
    (net (code "101") (name "unconnected-(U4A-PTE25{slash}ADC0_SE18-Pad32)") (class "Default")
      (node (ref "U4") (pin "32") (pinfunction "PTE25/ADC0_SE18_32") (pintype "bidirectional+no_connect"))
    )
    (net (code "102") (name "unconnected-(U4A-PTE26-Pad33)") (class "Default")
      (node (ref "U4") (pin "33") (pinfunction "PTE26_33") (pintype "bidirectional+no_connect"))
    )
    (net (code "103") (name "unconnected-(U4B-DAC0_OUT{slash}CMP1_IN3{slash}ADC0_SE23-Pad27)") (class "Default")
      (node (ref "U4") (pin "27") (pinfunction "DAC0_OUT/CMP1_IN3/ADC0_SE23_27") (pintype "bidirectional+no_connect"))
    )
    (net (code "104") (name "unconnected-(U4B-EXTAL32-Pad29)") (class "Default")
      (node (ref "U4") (pin "29") (pinfunction "EXTAL32_29") (pintype "passive+no_connect"))
    )
    (net (code "105") (name "unconnected-(U4B-USB0_DM-Pad11)") (class "Default")
      (node (ref "U4") (pin "11") (pinfunction "USB0_DM_11") (pintype "bidirectional+no_connect"))
    )
    (net (code "106") (name "unconnected-(U4B-USB0_DP-Pad10)") (class "Default")
      (node (ref "U4") (pin "10") (pinfunction "USB0_DP_10") (pintype "bidirectional+no_connect"))
    )
    (net (code "107") (name "unconnected-(U4B-VOUT33-Pad12)") (class "Default")
      (node (ref "U4") (pin "12") (pinfunction "VOUT33_12") (pintype "power_in+no_connect"))
    )
    (net (code "108") (name "unconnected-(U4B-VREF_OUT{slash}CMP1_IN5{slash}CMP0_IN5{slash}ADC1_SE18-Pad26)") (class "Default")
      (node (ref "U4") (pin "26") (pinfunction "VREF_OUT/CMP1_IN5/CMP0_IN5/ADC1_SE18_26") (pintype "bidirectional+no_connect"))
    )
    (net (code "109") (name "unconnected-(U4B-XTAL32-Pad28)") (class "Default")
      (node (ref "U4") (pin "28") (pinfunction "XTAL32_28") (pintype "passive+no_connect"))
    )
    (net (code "110") (name "unconnected-(U6-A1-Pad3)") (class "Default")
      (node (ref "U6") (pin "3") (pinfunction "A1_3") (pintype "bidirectional"))
    )
    (net (code "111") (name "unconnected-(U6-A2-Pad4)") (class "Default")
      (node (ref "U6") (pin "4") (pinfunction "A2_4") (pintype "bidirectional"))
    )
    (net (code "112") (name "unconnected-(U6-A3-Pad5)") (class "Default")
      (node (ref "U6") (pin "5") (pinfunction "A3_5") (pintype "bidirectional"))
    )
    (net (code "113") (name "unconnected-(U6-A4-Pad6)") (class "Default")
      (node (ref "U6") (pin "6") (pinfunction "A4_6") (pintype "bidirectional"))
    )
    (net (code "114") (name "unconnected-(U6-A5-Pad7)") (class "Default")
      (node (ref "U6") (pin "7") (pinfunction "A5_7") (pintype "bidirectional"))
    )
    (net (code "115") (name "unconnected-(U6-A6-Pad8)") (class "Default")
      (node (ref "U6") (pin "8") (pinfunction "A6_8") (pintype "bidirectional"))
    )
    (net (code "116") (name "unconnected-(U6-A7-Pad9)") (class "Default")
      (node (ref "U6") (pin "9") (pinfunction "A7_9") (pintype "bidirectional"))
    )
    (net (code "117") (name "unconnected-(U6-B1-Pad17)") (class "Default")
      (node (ref "U6") (pin "17") (pinfunction "B1_17") (pintype "bidirectional"))
    )
    (net (code "118") (name "unconnected-(U6-B2-Pad16)") (class "Default")
      (node (ref "U6") (pin "16") (pinfunction "B2_16") (pintype "bidirectional"))
    )
    (net (code "119") (name "unconnected-(U6-B3-Pad15)") (class "Default")
      (node (ref "U6") (pin "15") (pinfunction "B3_15") (pintype "bidirectional"))
    )
    (net (code "120") (name "unconnected-(U6-B4-Pad14)") (class "Default")
      (node (ref "U6") (pin "14") (pinfunction "B4_14") (pintype "bidirectional"))
    )
    (net (code "121") (name "unconnected-(U6-B5-Pad13)") (class "Default")
      (node (ref "U6") (pin "13") (pinfunction "B5_13") (pintype "bidirectional"))
    )
    (net (code "122") (name "unconnected-(U6-B6-Pad12)") (class "Default")
      (node (ref "U6") (pin "12") (pinfunction "B6_12") (pintype "bidirectional"))
    )
    (net (code "123") (name "unconnected-(U6-B7-Pad11)") (class "Default")
      (node (ref "U6") (pin "11") (pinfunction "B7_11") (pintype "bidirectional"))
    )
  )
)
